# TeamB_PowerBoard.net
KiCad netlist of a schematic drawn in EAGLE
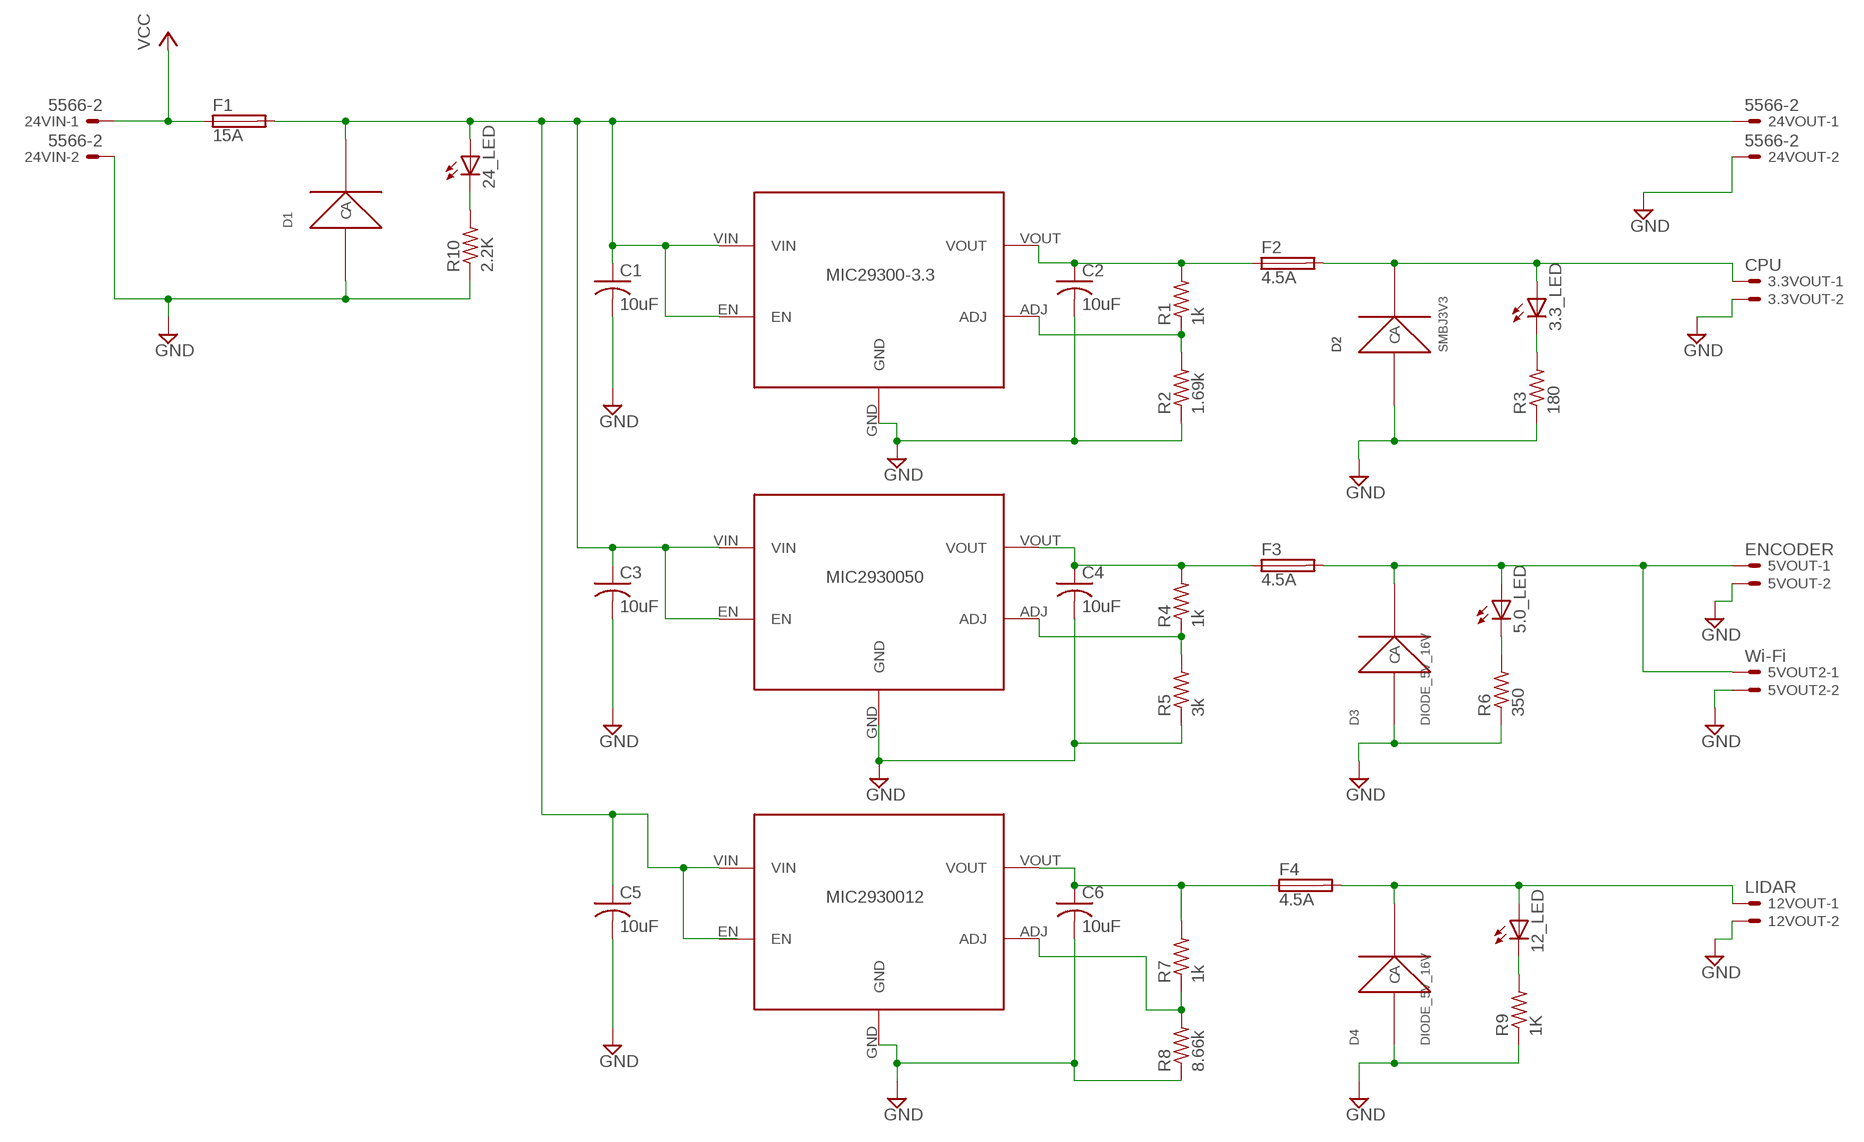
[diagram p0: schematic, sheet 1]

(export (version "E")
  (design (tool "Eeschema 10.0.6"))
  (components
    (comp (ref "3.3VOUT")
      (value "CPU")
      (footprint "eagle-import:70543-02")
      (libsource (lib "eagle-import") (part "C-GRID-02-70543"))
    )
    (comp (ref "3.3_LED")
      (value "LEDSML1206")
      (footprint "eagle-import:SML1206")
      (libsource (lib "eagle-import") (part "LEDSML1206"))
    )
    (comp (ref "5.0_LED")
      (value "LEDSML1206")
      (footprint "eagle-import:SML1206")
      (libsource (lib "eagle-import") (part "LEDSML1206"))
    )
    (comp (ref "5VOUT")
      (value "ENCODER")
      (footprint "eagle-import:70543-02")
      (libsource (lib "eagle-import") (part "C-GRID-02-70543"))
    )
    (comp (ref "5VOUT2")
      (value "Wi-Fi")
      (footprint "eagle-import:70543-02")
      (libsource (lib "eagle-import") (part "C-GRID-02-70543"))
    )
    (comp (ref "12VOUT")
      (value "LIDAR")
      (footprint "eagle-import:70543-02")
      (libsource (lib "eagle-import") (part "C-GRID-02-70543"))
    )
    (comp (ref "12_LED")
      (value "LEDSML1206")
      (footprint "eagle-import:SML1206")
      (libsource (lib "eagle-import") (part "LEDSML1206"))
    )
    (comp (ref "24VIN")
      (value "5566-2")
      (footprint "eagle-import:5566-2")
      (libsource (lib "eagle-import") (part "5566-2"))
    )
    (comp (ref "24VOUT")
      (value "5566-2")
      (footprint "eagle-import:5566-2")
      (libsource (lib "eagle-import") (part "5566-2"))
    )
    (comp (ref "24_LED")
      (value "LEDSML1206")
      (footprint "eagle-import:SML1206")
      (libsource (lib "eagle-import") (part "LEDSML1206"))
    )
    (comp (ref "C1")
      (value "10uF")
      (footprint "eagle-import:C2220K")
      (libsource (lib "eagle-import") (part "C-USC2220K"))
    )
    (comp (ref "C2")
      (value "10uF")
      (footprint "eagle-import:C2220K")
      (libsource (lib "eagle-import") (part "C-USC2220K"))
    )
    (comp (ref "C3")
      (value "10uF")
      (footprint "eagle-import:C2220K")
      (libsource (lib "eagle-import") (part "C-USC2220K"))
    )
    (comp (ref "C4")
      (value "10uF")
      (footprint "eagle-import:C2220K")
      (libsource (lib "eagle-import") (part "C-USC2220K"))
    )
    (comp (ref "C5")
      (value "10uF")
      (footprint "eagle-import:C2220K")
      (libsource (lib "eagle-import") (part "C-USC2220K"))
    )
    (comp (ref "C6")
      (value "10uF")
      (footprint "eagle-import:C2220K")
      (libsource (lib "eagle-import") (part "C-USC2220K"))
    )
    (comp (ref "D1")
      (value "DIODE_26")
      (footprint "eagle-import:DIODE_26")
      (libsource (lib "eagle-import") (part "DIODE_26"))
    )
    (comp (ref "D2")
      (value "SMBJ3V3")
      (footprint "eagle-import:SMBJ3V3")
      (libsource (lib "eagle-import") (part "SMBJ3V3"))
    )
    (comp (ref "D3")
      (value "DIODE_5V_16V")
      (footprint "eagle-import:DIODE_5V_16V")
      (libsource (lib "eagle-import") (part "DIODE_5V_16V"))
    )
    (comp (ref "D4")
      (value "DIODE_5V_16V")
      (footprint "eagle-import:DIODE_5V_16V")
      (libsource (lib "eagle-import") (part "DIODE_5V_16V"))
    )
    (comp (ref "F1")
      (value "15A")
      (footprint "eagle-import:TE5")
      (libsource (lib "eagle-import") (part "TE5"))
    )
    (comp (ref "F2")
      (value "4.5A")
      (footprint "eagle-import:TE5")
      (libsource (lib "eagle-import") (part "TE5"))
    )
    (comp (ref "F3")
      (value "4.5A")
      (footprint "eagle-import:TE5")
      (libsource (lib "eagle-import") (part "TE5"))
    )
    (comp (ref "F4")
      (value "4.5A")
      (footprint "eagle-import:TE5")
      (libsource (lib "eagle-import") (part "TE5"))
    )
    (comp (ref "R1")
      (value "1k")
      (footprint "eagle-import:R1206")
      (libsource (lib "eagle-import") (part "R-US_R1206"))
    )
    (comp (ref "R2")
      (value "1.69k")
      (footprint "eagle-import:R1206")
      (libsource (lib "eagle-import") (part "R-US_R1206"))
    )
    (comp (ref "R3")
      (value "180")
      (footprint "eagle-import:R1206")
      (libsource (lib "eagle-import") (part "R-US_R1206"))
    )
    (comp (ref "R4")
      (value "1k")
      (footprint "eagle-import:R1206")
      (libsource (lib "eagle-import") (part "R-US_R1206"))
    )
    (comp (ref "R5")
      (value "3k")
      (footprint "eagle-import:R1206")
      (libsource (lib "eagle-import") (part "R-US_R1206"))
    )
    (comp (ref "R6")
      (value "350")
      (footprint "eagle-import:R1206")
      (libsource (lib "eagle-import") (part "R-US_R1206"))
    )
    (comp (ref "R7")
      (value "1k")
      (footprint "eagle-import:R1206")
      (libsource (lib "eagle-import") (part "R-US_R1206"))
    )
    (comp (ref "R8")
      (value "8.66k")
      (footprint "eagle-import:R1206")
      (libsource (lib "eagle-import") (part "R-US_R1206"))
    )
    (comp (ref "R9")
      (value "1K")
      (footprint "eagle-import:R1206")
      (libsource (lib "eagle-import") (part "R-US_R1206"))
    )
    (comp (ref "R10")
      (value "2.2K")
      (footprint "eagle-import:R1206")
      (libsource (lib "eagle-import") (part "R-US_R1206"))
    )
    (comp (ref "U$1")
      (value "MIC29300")
      (footprint "eagle-import:MIC29300WU")
      (libsource (lib "eagle-import") (part "MIC2930033WU_MIC29300"))
    )
    (comp (ref "U$2")
      (value "MIC29300")
      (footprint "eagle-import:MIC29300WU")
      (libsource (lib "eagle-import") (part "MIC2930050WU_MIC29300"))
    )
    (comp (ref "U$3")
      (value "MIC29300")
      (footprint "eagle-import:MIC29300WU")
      (libsource (lib "eagle-import") (part "MIC29300"))
    )
  )
  (nets
    (net (code "1") (name "GND") (class "Default")
      (node (ref "12VOUT") (pin "2") (pinfunction "S_2") (pintype "passive"))
      (node (ref "24VIN") (pin "2") (pinfunction "S_2") (pintype "passive"))
      (node (ref "24VOUT") (pin "2") (pinfunction "S_2") (pintype "passive"))
      (node (ref "3.3VOUT") (pin "2") (pinfunction "S_2") (pintype "passive"))
      (node (ref "5VOUT") (pin "2") (pinfunction "S_2") (pintype "passive"))
      (node (ref "5VOUT2") (pin "2") (pinfunction "S_2") (pintype "passive"))
      (node (ref "C1") (pin "2") (pinfunction "2_2") (pintype "passive"))
      (node (ref "C2") (pin "2") (pinfunction "2_2") (pintype "passive"))
      (node (ref "C3") (pin "2") (pinfunction "2_2") (pintype "passive"))
      (node (ref "C4") (pin "2") (pinfunction "2_2") (pintype "passive"))
      (node (ref "C5") (pin "2") (pinfunction "2_2") (pintype "passive"))
      (node (ref "C6") (pin "2") (pinfunction "2_2") (pintype "passive"))
      (node (ref "D1") (pin "1") (pinfunction "A_1") (pintype "bidirectional"))
      (node (ref "D2") (pin "1") (pinfunction "A_1") (pintype "bidirectional"))
      (node (ref "D3") (pin "1") (pinfunction "A_1") (pintype "bidirectional"))
      (node (ref "D4") (pin "1") (pinfunction "A_1") (pintype "bidirectional"))
      (node (ref "R10") (pin "1") (pinfunction "1_1") (pintype "passive"))
      (node (ref "R2") (pin "1") (pinfunction "1_1") (pintype "passive"))
      (node (ref "R3") (pin "1") (pinfunction "1_1") (pintype "passive"))
      (node (ref "R5") (pin "1") (pinfunction "1_1") (pintype "passive"))
      (node (ref "R6") (pin "1") (pinfunction "1_1") (pintype "passive"))
      (node (ref "R8") (pin "1") (pinfunction "1_1") (pintype "passive"))
      (node (ref "R9") (pin "1") (pinfunction "1_1") (pintype "passive"))
      (node (ref "U$1") (pin "GND") (pinfunction "GND_GND") (pintype "bidirectional"))
      (node (ref "U$2") (pin "GND") (pinfunction "GND_GND") (pintype "bidirectional"))
      (node (ref "U$3") (pin "GND") (pinfunction "GND_GND") (pintype "bidirectional"))
    )
    (net (code "2") (name "Net-(3.3VOUTA-S)") (class "Default")
      (node (ref "3.3VOUT") (pin "1") (pinfunction "S_1") (pintype "passive"))
      (node (ref "3.3_LED") (pin "A") (pinfunction "A_A") (pintype "passive"))
      (node (ref "D2") (pin "2") (pinfunction "C_2") (pintype "bidirectional"))
      (node (ref "F2") (pin "2") (pinfunction "2_2") (pintype "passive"))
    )
    (net (code "3") (name "Net-(3.3_LED-PadC)") (class "Default")
      (node (ref "3.3_LED") (pin "C") (pinfunction "C_C") (pintype "passive"))
      (node (ref "R3") (pin "2") (pinfunction "2_2") (pintype "passive"))
    )
    (net (code "4") (name "Net-(5.0_LED-PadC)") (class "Default")
      (node (ref "5.0_LED") (pin "C") (pinfunction "C_C") (pintype "passive"))
      (node (ref "R6") (pin "2") (pinfunction "2_2") (pintype "passive"))
    )
    (net (code "5") (name "Net-(5VOUT2A-S)") (class "Default")
      (node (ref "5.0_LED") (pin "A") (pinfunction "A_A") (pintype "passive"))
      (node (ref "5VOUT") (pin "1") (pinfunction "S_1") (pintype "passive"))
      (node (ref "5VOUT2") (pin "1") (pinfunction "S_1") (pintype "passive"))
      (node (ref "D3") (pin "2") (pinfunction "C_2") (pintype "bidirectional"))
      (node (ref "F3") (pin "2") (pinfunction "2_2") (pintype "passive"))
    )
    (net (code "6") (name "Net-(12VOUTA-S)") (class "Default")
      (node (ref "12VOUT") (pin "1") (pinfunction "S_1") (pintype "passive"))
      (node (ref "12_LED") (pin "A") (pinfunction "A_A") (pintype "passive"))
      (node (ref "D4") (pin "2") (pinfunction "C_2") (pintype "bidirectional"))
      (node (ref "F4") (pin "2") (pinfunction "2_2") (pintype "passive"))
    )
    (net (code "7") (name "Net-(12_LED-PadC)") (class "Default")
      (node (ref "12_LED") (pin "C") (pinfunction "C_C") (pintype "passive"))
      (node (ref "R9") (pin "2") (pinfunction "2_2") (pintype "passive"))
    )
    (net (code "8") (name "Net-(24VOUTA-S)") (class "Default")
      (node (ref "24VOUT") (pin "1") (pinfunction "S_1") (pintype "passive"))
      (node (ref "24_LED") (pin "A") (pinfunction "A_A") (pintype "passive"))
      (node (ref "C1") (pin "1") (pinfunction "1_1") (pintype "passive"))
      (node (ref "C3") (pin "1") (pinfunction "1_1") (pintype "passive"))
      (node (ref "C5") (pin "1") (pinfunction "1_1") (pintype "passive"))
      (node (ref "D1") (pin "2") (pinfunction "C_2") (pintype "bidirectional"))
      (node (ref "F1") (pin "2") (pinfunction "2_2") (pintype "passive"))
      (node (ref "U$1") (pin "EN") (pinfunction "EN_EN") (pintype "bidirectional"))
      (node (ref "U$1") (pin "VIN") (pinfunction "VIN_VIN") (pintype "bidirectional"))
      (node (ref "U$2") (pin "EN") (pinfunction "EN_EN") (pintype "bidirectional"))
      (node (ref "U$2") (pin "VIN") (pinfunction "VIN_VIN") (pintype "bidirectional"))
      (node (ref "U$3") (pin "VIN") (pinfunction "VIN_VIN") (pintype "bidirectional"))
    )
    (net (code "9") (name "Net-(24_LED-PadC)") (class "Default")
      (node (ref "24_LED") (pin "C") (pinfunction "C_C") (pintype "passive"))
      (node (ref "R10") (pin "2") (pinfunction "2_2") (pintype "passive"))
    )
    (net (code "10") (name "Net-(C2-Pad1)") (class "Default")
      (node (ref "C2") (pin "1") (pinfunction "1_1") (pintype "passive"))
      (node (ref "F2") (pin "1") (pinfunction "1_1") (pintype "passive"))
      (node (ref "R1") (pin "2") (pinfunction "2_2") (pintype "passive"))
      (node (ref "U$1") (pin "VOUT") (pinfunction "VOUT_VOUT") (pintype "bidirectional"))
    )
    (net (code "11") (name "Net-(C4-Pad1)") (class "Default")
      (node (ref "C4") (pin "1") (pinfunction "1_1") (pintype "passive"))
      (node (ref "F3") (pin "1") (pinfunction "1_1") (pintype "passive"))
      (node (ref "R4") (pin "2") (pinfunction "2_2") (pintype "passive"))
      (node (ref "U$2") (pin "VOUT") (pinfunction "VOUT_VOUT") (pintype "bidirectional"))
    )
    (net (code "12") (name "Net-(C6-Pad1)") (class "Default")
      (node (ref "C6") (pin "1") (pinfunction "1_1") (pintype "passive"))
      (node (ref "F4") (pin "1") (pinfunction "1_1") (pintype "passive"))
      (node (ref "R7") (pin "2") (pinfunction "2_2") (pintype "passive"))
      (node (ref "U$3") (pin "VOUT") (pinfunction "VOUT_VOUT") (pintype "bidirectional"))
    )
    (net (code "13") (name "Net-(R1-Pad1)") (class "Default")
      (node (ref "R1") (pin "1") (pinfunction "1_1") (pintype "passive"))
      (node (ref "R2") (pin "2") (pinfunction "2_2") (pintype "passive"))
      (node (ref "U$1") (pin "ADJ") (pinfunction "ADJ_ADJ") (pintype "bidirectional"))
    )
    (net (code "14") (name "Net-(R4-Pad1)") (class "Default")
      (node (ref "R4") (pin "1") (pinfunction "1_1") (pintype "passive"))
      (node (ref "R5") (pin "2") (pinfunction "2_2") (pintype "passive"))
      (node (ref "U$2") (pin "ADJ") (pinfunction "ADJ_ADJ") (pintype "bidirectional"))
    )
    (net (code "15") (name "Net-(R7-Pad1)") (class "Default")
      (node (ref "R7") (pin "1") (pinfunction "1_1") (pintype "passive"))
      (node (ref "R8") (pin "2") (pinfunction "2_2") (pintype "passive"))
      (node (ref "U$3") (pin "ADJ") (pinfunction "ADJ_ADJ") (pintype "bidirectional"))
    )
    (net (code "16") (name "VCC") (class "Default")
      (node (ref "24VIN") (pin "1") (pinfunction "S_1") (pintype "passive"))
      (node (ref "F1") (pin "1") (pinfunction "1_1") (pintype "passive"))
    )
    (net (code "17") (name "unconnected-(U$3-PadEN)") (class "Default")
      (node (ref "U$3") (pin "EN") (pinfunction "EN_EN") (pintype "bidirectional"))
    )
  )
)
